# 06_-_HDMI_OUTPUT.net
KiCad netlist of a schematic drawn in Altium Designer
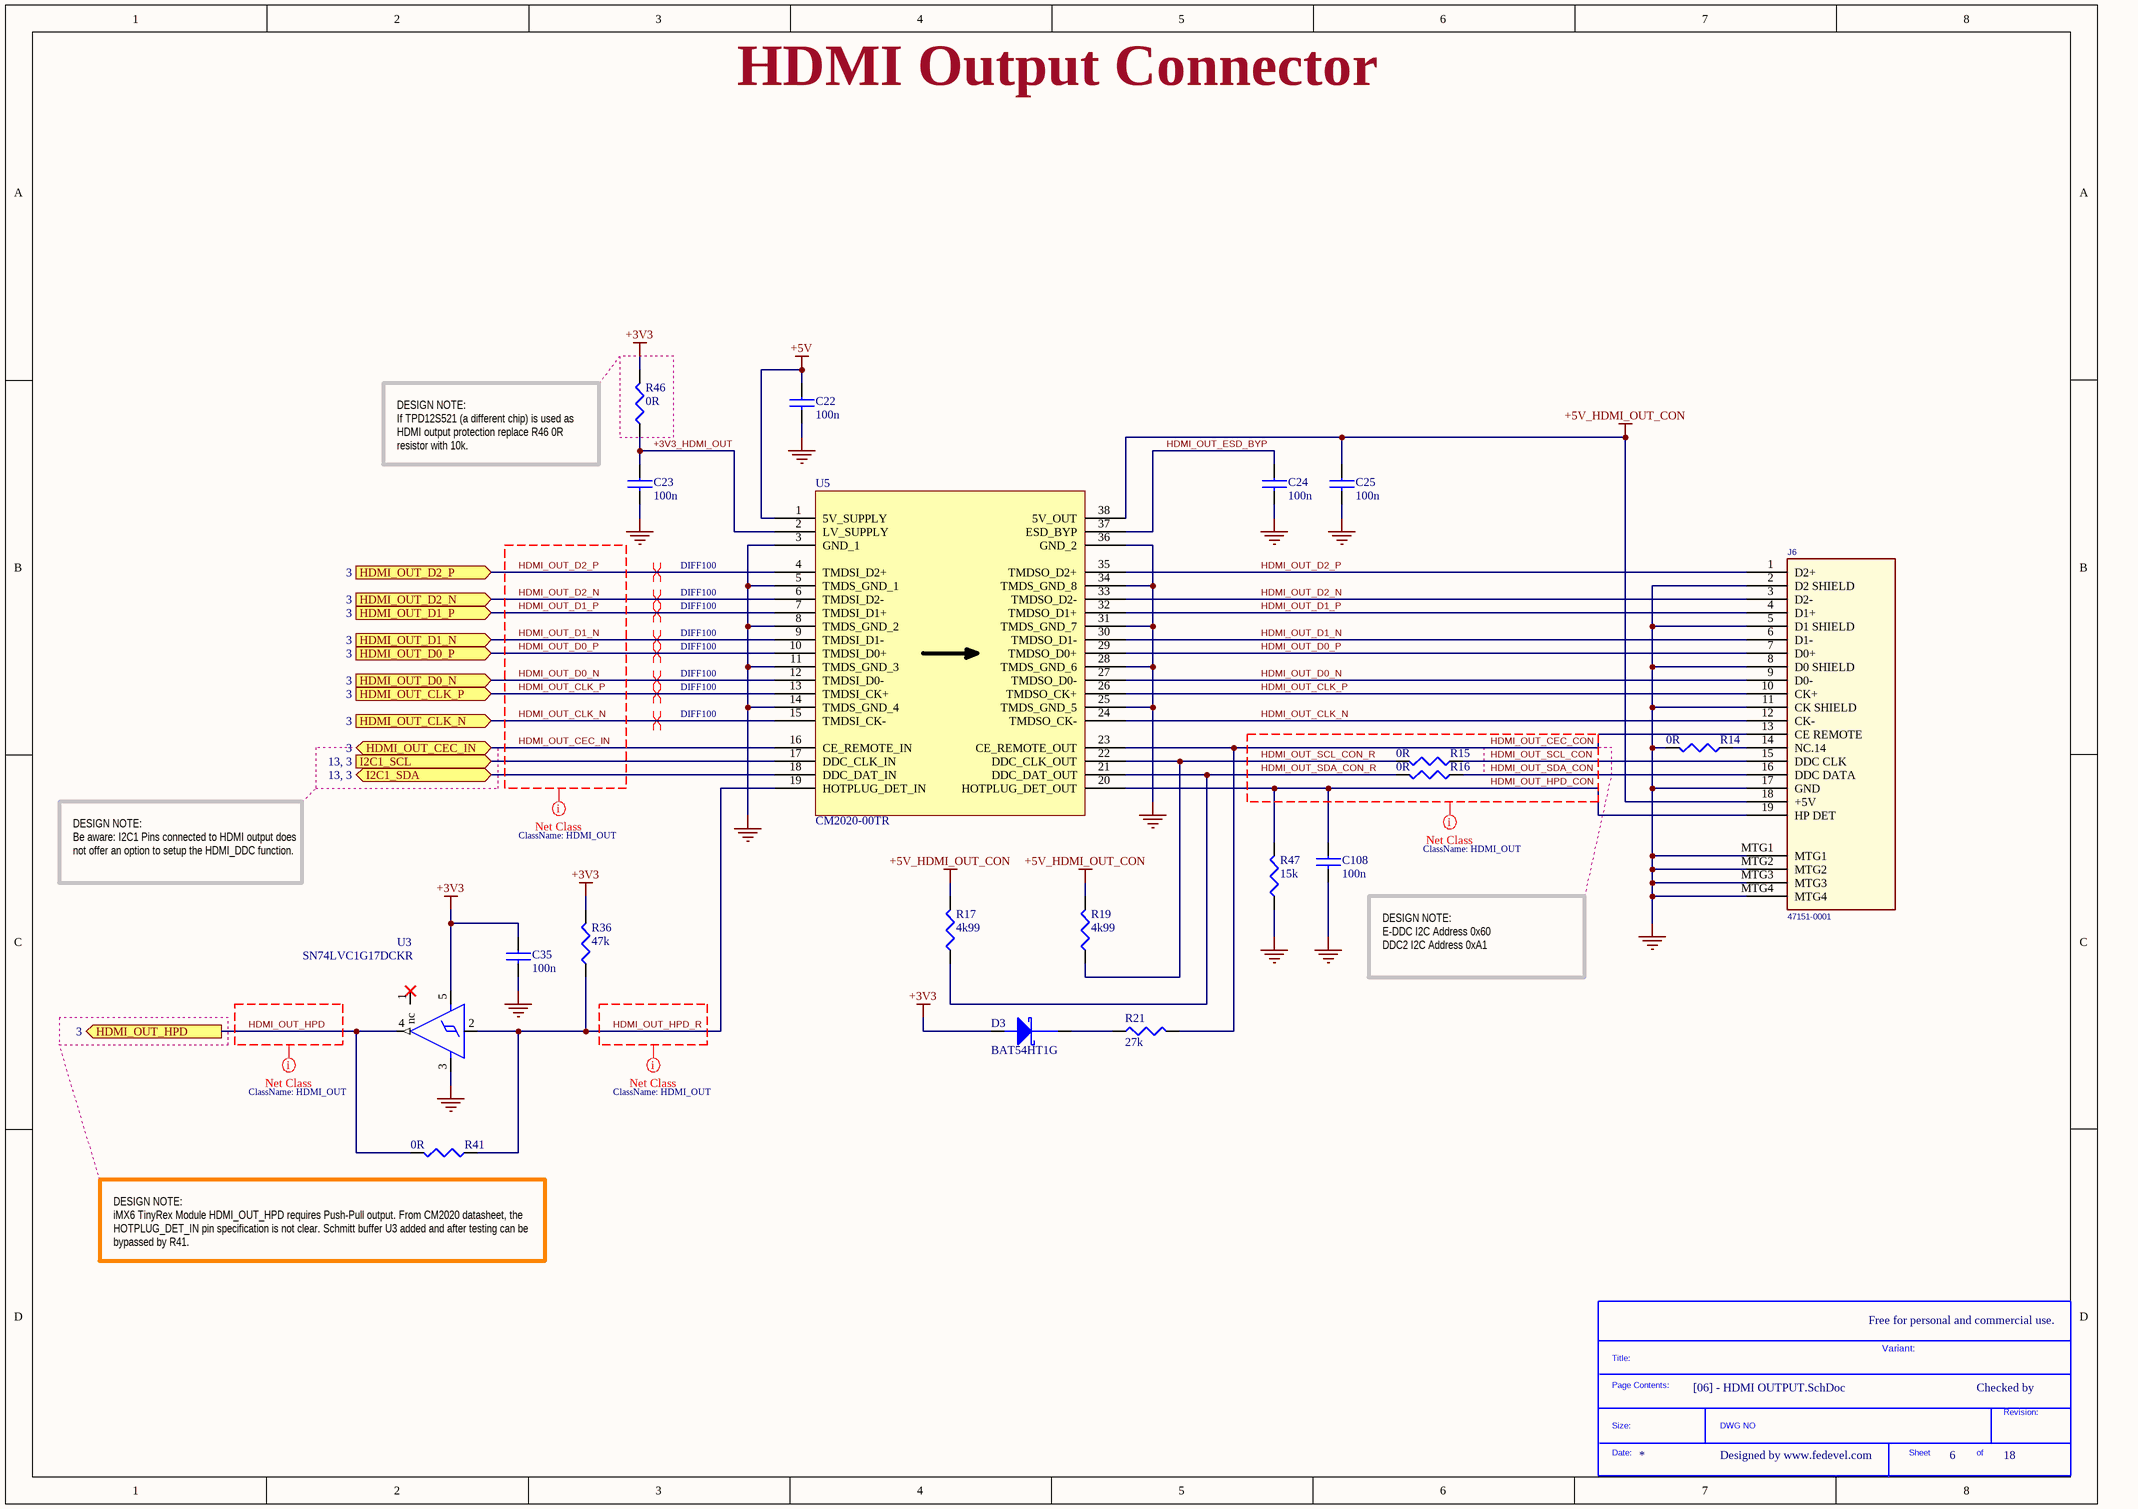
[diagram p0: [06] - HDMI OUTPUT.SchDoc]

(export (version "E")
  (design (tool "Eeschema 10.0.6"))
  (components
    (comp (ref "*") (value "SDTitleBlock") (libsource (lib "*") (part "SDTitleBlock")))
    (comp (ref "C22")
      (value "100n")
      (footprint "C0402")
      (description "CAP CER .10UF 50V X5R 10% 0402")
      (fields
        (field (name "MANUFACTURER") "TDK Corporation")
        (field (name "MANUFACTURER PART NUMBER") "C1005X5R1H104K")
      )
      (libsource (lib "Integrated_Library_FEDEVEL_APR_2015") (part "C1005X5R1H104K"))
    )
    (comp (ref "C23")
      (value "100n")
      (footprint "C0402")
      (description "CAP CER .10UF 50V X5R 10% 0402")
      (fields
        (field (name "MANUFACTURER") "TDK Corporation")
        (field (name "MANUFACTURER PART NUMBER") "C1005X5R1H104K")
      )
      (libsource (lib "Integrated_Library_FEDEVEL_APR_2015") (part "C1005X5R1H104K"))
    )
    (comp (ref "C24")
      (value "100n")
      (footprint "C0402")
      (description "CAP CER .10UF 50V X5R 10% 0402")
      (fields
        (field (name "MANUFACTURER") "TDK Corporation")
        (field (name "MANUFACTURER PART NUMBER") "C1005X5R1H104K")
      )
      (libsource (lib "Integrated_Library_FEDEVEL_APR_2015") (part "C1005X5R1H104K"))
    )
    (comp (ref "C25")
      (value "100n")
      (footprint "C0402")
      (description "CAP CER .10UF 50V X5R 10% 0402")
      (fields
        (field (name "MANUFACTURER") "TDK Corporation")
        (field (name "MANUFACTURER PART NUMBER") "C1005X5R1H104K")
      )
      (libsource (lib "Integrated_Library_FEDEVEL_APR_2015") (part "C1005X5R1H104K"))
    )
    (comp (ref "C35")
      (value "100n")
      (footprint "C0402")
      (description "CAP CER .10UF 50V X5R 10% 0402")
      (fields
        (field (name "MANUFACTURER") "TDK Corporation")
        (field (name "MANUFACTURER PART NUMBER") "C1005X5R1H104K")
      )
      (libsource (lib "Integrated_Library_FEDEVEL_APR_2015") (part "C1005X5R1H104K"))
    )
    (comp (ref "C108")
      (value "100n")
      (footprint "C0402")
      (description "CAP CER .10UF 50V X5R 10% 0402")
      (fields
        (field (name "MANUFACTURER") "TDK Corporation")
        (field (name "MANUFACTURER PART NUMBER") "C1005X5R1H104K")
      )
      (libsource (lib "Integrated_Library_FEDEVEL_APR_2015") (part "C1005X5R1H104K"))
    )
    (comp (ref "D3")
      (value "BAT54HT1G")
      (footprint "SOD323")
      (description "DIODE SCHOTTKY 30V 0.2A SOD323")
      (fields (field (name "MANUFACTURER") "Fairchild Semiconductor") (field (name ".CREATOR") "MM"))
      (libsource (lib "Integrated_Library_FEDEVEL_APR_2015") (part "BAT54HT1G"))
    )
    (comp (ref "J6")
      (value "47151-0001")
      (footprint "HDMI V1.1")
      (description "CONN RCPT 19POS HDMI RT ANG SMD")
      (fields
        (field (name "MANUFACTURER") "Molex Connector Corporation")
        (field (name ".CHECKED PCB") "MM")
        (field (name ".CHECKED SCH") "MM")
      )
      (libsource (lib "Integrated_Library_FEDEVEL_APR_2015") (part "47151-0001_v1.1"))
    )
    (comp (ref "R14")
      (value "0R")
      (footprint "R0402")
      (description "RES 0.0 OHM 1/16W 0402 SMD")
      (fields
        (field (name "MANUFACTURER") "Yageo")
        (field (name "MANUFACTURER PART NUMBER") "RC0402JR-070RL")
      )
      (libsource (lib "Integrated_Library_FEDEVEL_APR_2015") (part "RC0402JR-070RL"))
    )
    (comp (ref "R15")
      (value "0R")
      (footprint "R0402")
      (description "RES 0.0 OHM 1/16W 0402 SMD")
      (fields
        (field (name "MANUFACTURER") "Yageo")
        (field (name "MANUFACTURER PART NUMBER") "RC0402JR-070RL")
      )
      (libsource (lib "Integrated_Library_FEDEVEL_APR_2015") (part "RC0402JR-070RL"))
    )
    (comp (ref "R16")
      (value "0R")
      (footprint "R0402")
      (description "RES 0.0 OHM 1/16W 0402 SMD")
      (fields
        (field (name "MANUFACTURER") "Yageo")
        (field (name "MANUFACTURER PART NUMBER") "RC0402JR-070RL")
      )
      (libsource (lib "Integrated_Library_FEDEVEL_APR_2015") (part "RC0402JR-070RL"))
    )
    (comp (ref "R17")
      (value "4k99")
      (footprint "R0402")
      (description "RES TF 4.99K OHM 1% 1/16W 0402")
      (fields
        (field (name "MANUFACTURER") "Stackpole Electronics Inc")
        (field (name "MANUFACTURER PART NUMBER") "RMCF0402FT4K99")
      )
      (libsource (lib "Integrated_Library_FEDEVEL_APR_2015") (part "RMCF0402FT4K99"))
    )
    (comp (ref "R19")
      (value "4k99")
      (footprint "R0402")
      (description "RES TF 4.99K OHM 1% 1/16W 0402")
      (fields
        (field (name "MANUFACTURER") "Stackpole Electronics Inc")
        (field (name "MANUFACTURER PART NUMBER") "RMCF0402FT4K99")
      )
      (libsource (lib "Integrated_Library_FEDEVEL_APR_2015") (part "RMCF0402FT4K99"))
    )
    (comp (ref "R21")
      (value "27k")
      (footprint "R0402")
      (description "RES 27.0K OHM 1/16W 1% 0402 SMD")
      (fields
        (field (name "MANUFACTURER") "Yageo")
        (field (name "MANUFACTURER PART NUMBER") "RC0402FR-0727KL")
      )
      (libsource (lib "Integrated_Library_FEDEVEL_APR_2015") (part "RC0402FR-0727KL"))
    )
    (comp (ref "R36")
      (value "47k")
      (footprint "R0402")
      (description "RES 47.0K OHM 1/16W 1% 0402 SMD")
      (fields
        (field (name "MANUFACTURER") "Yageo")
        (field (name "MANUFACTURER PART NUMBER") "RC0402FR-0747KL")
      )
      (libsource (lib "Integrated_Library_FEDEVEL_APR_2015") (part "RC0402FR-0747KL"))
    )
    (comp (ref "R41")
      (value "0R")
      (footprint "R0402")
      (description "RES 0.0 OHM 1/16W 0402 SMD")
      (fields
        (field (name "MANUFACTURER") "Yageo")
        (field (name "MANUFACTURER PART NUMBER") "RC0402JR-070RL")
      )
      (libsource (lib "Integrated_Library_FEDEVEL_APR_2015") (part "RC0402JR-070RL"))
    )
    (comp (ref "R46")
      (value "0R")
      (footprint "R0402")
      (description "RES 0.0 OHM 1/16W 0402 SMD")
      (fields
        (field (name "MANUFACTURER") "Yageo")
        (field (name "MANUFACTURER PART NUMBER") "RC0402JR-070RL")
      )
      (libsource (lib "Integrated_Library_FEDEVEL_APR_2015") (part "RC0402JR-070RL"))
    )
    (comp (ref "R47")
      (value "15k")
      (footprint "R0402")
      (description "RES 15.0K OHM 1/16W 1% 0402 SMD")
      (fields
        (field (name "MANUFACTURER") "Yageo")
        (field (name "MANUFACTURER PART NUMBER") "RC0402FR-0715KL")
      )
      (libsource (lib "Integrated_Library_FEDEVEL_APR_2015") (part "RC0402FR-0715KL"))
    )
    (comp (ref "U3")
      (value "SN74LVC1G17DCKR")
      (footprint "SC70_5")
      (description "IC BUFFER SCHMIT TRIG SC705")
      (fields
        (field (name "MANUFACTURER") "Texas Instruments")
        (field (name ".CHECKED PCB") "RF")
        (field (name ".CHECKED SCH") "RF")
      )
      (libsource (lib "Integrated_Library_FEDEVEL_APR_2015") (part "SN74LVC1G17DCKR"))
    )
    (comp (ref "U5")
      (value "CM2020-00TR")
      (footprint "TSSOP_38")
      (description "IC HDMI TX PORT P/I 38-TSSOP")
      (fields (field (name "MANUFACTURER") "ON Semiconductor") (field (name ".CREATOR") "MM"))
      (libsource (lib "Integrated_Library_FEDEVEL_APR_2015") (part "CM2020-00TR"))
    )
  )
  (nets
    (net (code "1") (name "+3V3") (class "Default")
      (node (ref "C35") (pin "1") (pinfunction "1_1") (pintype "passive"))
      (node (ref "D3") (pin "2") (pinfunction "Anode_2") (pintype "passive"))
      (node (ref "R36") (pin "2") (pinfunction "2_2") (pintype "passive"))
      (node (ref "R46") (pin "2") (pinfunction "2_2") (pintype "passive"))
      (node (ref "U3") (pin "5") (pinfunction "NC1_5") (pintype "passive"))
    )
    (net (code "2") (name "+5V") (class "Default")
      (node (ref "C22") (pin "1") (pinfunction "1_1") (pintype "passive"))
      (node (ref "U5") (pin "1") (pinfunction "5V_SUPPLY_1") (pintype "passive"))
    )
    (net (code "3") (name "+5V_HDMI_OUT_CON") (class "Default")
      (node (ref "C25") (pin "1") (pinfunction "1_1") (pintype "passive"))
      (node (ref "J6") (pin "18") (pinfunction "+5V_18") (pintype "passive"))
      (node (ref "R17") (pin "2") (pinfunction "2_2") (pintype "passive"))
      (node (ref "R19") (pin "2") (pinfunction "2_2") (pintype "passive"))
      (node (ref "U5") (pin "38") (pinfunction "5V_OUT_38") (pintype "passive"))
    )
    (net (code "4") (name "/+3V3_HDMI_OUT") (class "Default")
      (node (ref "C23") (pin "1") (pinfunction "1_1") (pintype "passive"))
      (node (ref "R46") (pin "1") (pinfunction "1_1") (pintype "passive"))
      (node (ref "U5") (pin "2") (pinfunction "LV_SUPPLY_2") (pintype "passive"))
    )
    (net (code "5") (name "/HDMI_OUT_CEC_CON") (class "Default")
      (node (ref "J6") (pin "13") (pinfunction "CE_REMOTE_13") (pintype "passive"))
      (node (ref "R21") (pin "2") (pinfunction "2_2") (pintype "passive"))
      (node (ref "U5") (pin "23") (pinfunction "CE_REMOTE_OUT_23") (pintype "passive"))
    )
    (net (code "6") (name "/HDMI_OUT_CEC_IN") (class "Default")
      (node (ref "U5") (pin "16") (pinfunction "CE_REMOTE_IN_16") (pintype "passive"))
    )
    (net (code "7") (name "/HDMI_OUT_CLK_N") (class "Default")
      (node (ref "J6") (pin "12") (pinfunction "CK-_12") (pintype "passive"))
      (node (ref "U5") (pin "15") (pinfunction "TMDSI_CK-_15") (pintype "passive"))
      (node (ref "U5") (pin "24") (pinfunction "TMDSO_CK-_24") (pintype "passive"))
    )
    (net (code "8") (name "/HDMI_OUT_CLK_P") (class "Default")
      (node (ref "J6") (pin "10") (pinfunction "CK+_10") (pintype "passive"))
      (node (ref "U5") (pin "13") (pinfunction "TMDSI_CK+_13") (pintype "passive"))
      (node (ref "U5") (pin "26") (pinfunction "TMDSO_CK+_26") (pintype "passive"))
    )
    (net (code "9") (name "/HDMI_OUT_D0_N") (class "Default")
      (node (ref "J6") (pin "9") (pinfunction "D0-_9") (pintype "passive"))
      (node (ref "U5") (pin "12") (pinfunction "TMDSI_D0-_12") (pintype "passive"))
      (node (ref "U5") (pin "27") (pinfunction "TMDSO_D0-_27") (pintype "passive"))
    )
    (net (code "10") (name "/HDMI_OUT_D0_P") (class "Default")
      (node (ref "J6") (pin "7") (pinfunction "D0+_7") (pintype "passive"))
      (node (ref "U5") (pin "10") (pinfunction "TMDSI_D0+_10") (pintype "passive"))
      (node (ref "U5") (pin "29") (pinfunction "TMDSO_D0+_29") (pintype "passive"))
    )
    (net (code "11") (name "/HDMI_OUT_D1_N") (class "Default")
      (node (ref "J6") (pin "6") (pinfunction "D1-_6") (pintype "passive"))
      (node (ref "U5") (pin "30") (pinfunction "TMDSO_D1-_30") (pintype "passive"))
      (node (ref "U5") (pin "9") (pinfunction "TMDSI_D1-_9") (pintype "passive"))
    )
    (net (code "12") (name "/HDMI_OUT_D1_P") (class "Default")
      (node (ref "J6") (pin "4") (pinfunction "D1+_4") (pintype "passive"))
      (node (ref "U5") (pin "32") (pinfunction "TMDSO_D1+_32") (pintype "passive"))
      (node (ref "U5") (pin "7") (pinfunction "TMDSI_D1+_7") (pintype "passive"))
    )
    (net (code "13") (name "/HDMI_OUT_D2_N") (class "Default")
      (node (ref "J6") (pin "3") (pinfunction "D2-_3") (pintype "passive"))
      (node (ref "U5") (pin "33") (pinfunction "TMDSO_D2-_33") (pintype "passive"))
      (node (ref "U5") (pin "6") (pinfunction "TMDSI_D2-_6") (pintype "passive"))
    )
    (net (code "14") (name "/HDMI_OUT_D2_P") (class "Default")
      (node (ref "J6") (pin "1") (pinfunction "D2+_1") (pintype "passive"))
      (node (ref "U5") (pin "35") (pinfunction "TMDSO_D2+_35") (pintype "passive"))
      (node (ref "U5") (pin "4") (pinfunction "TMDSI_D2+_4") (pintype "passive"))
    )
    (net (code "15") (name "/HDMI_OUT_ESD_BYP") (class "Default")
      (node (ref "C24") (pin "1") (pinfunction "1_1") (pintype "passive"))
      (node (ref "U5") (pin "37") (pinfunction "ESD_BYP_37") (pintype "passive"))
    )
    (net (code "16") (name "/HDMI_OUT_HPD") (class "Default")
      (node (ref "R41") (pin "2") (pinfunction "2_2") (pintype "passive"))
      (node (ref "U3") (pin "4") (pinfunction "O_4") (pintype "output"))
    )
    (net (code "17") (name "/HDMI_OUT_HPD_CON") (class "Default")
      (node (ref "C108") (pin "1") (pinfunction "1_1") (pintype "passive"))
      (node (ref "J6") (pin "19") (pinfunction "HP_DET_19") (pintype "passive"))
      (node (ref "R47") (pin "2") (pinfunction "2_2") (pintype "passive"))
      (node (ref "U5") (pin "20") (pinfunction "HOTPLUG_DET_OUT_20") (pintype "passive"))
    )
    (net (code "18") (name "/HDMI_OUT_HPD_R") (class "Default")
      (node (ref "R36") (pin "1") (pinfunction "1_1") (pintype "passive"))
      (node (ref "R41") (pin "1") (pinfunction "1_1") (pintype "passive"))
      (node (ref "U3") (pin "2") (pinfunction "I_2") (pintype "passive"))
      (node (ref "U5") (pin "19") (pinfunction "HOTPLUG_DET_IN_19") (pintype "passive"))
    )
    (net (code "19") (name "/HDMI_OUT_SCL_CON") (class "Default")
      (node (ref "J6") (pin "15") (pinfunction "DDC_CLK_15") (pintype "passive"))
      (node (ref "R15") (pin "1") (pinfunction "1_1") (pintype "passive"))
    )
    (net (code "20") (name "/HDMI_OUT_SCL_CON_R") (class "Default")
      (node (ref "R15") (pin "2") (pinfunction "2_2") (pintype "passive"))
      (node (ref "R19") (pin "1") (pinfunction "1_1") (pintype "passive"))
      (node (ref "U5") (pin "22") (pinfunction "DDC_CLK_OUT_22") (pintype "passive"))
    )
    (net (code "21") (name "/HDMI_OUT_SDA_CON") (class "Default")
      (node (ref "J6") (pin "16") (pinfunction "DDC_DATA_16") (pintype "passive"))
      (node (ref "R16") (pin "1") (pinfunction "1_1") (pintype "passive"))
    )
    (net (code "22") (name "/HDMI_OUT_SDA_CON_R") (class "Default")
      (node (ref "R16") (pin "2") (pinfunction "2_2") (pintype "passive"))
      (node (ref "R17") (pin "1") (pinfunction "1_1") (pintype "passive"))
      (node (ref "U5") (pin "21") (pinfunction "DDC_DAT_OUT_21") (pintype "passive"))
    )
    (net (code "23") (name "/I2C1_SCL") (class "Default")
      (node (ref "U5") (pin "17") (pinfunction "DDC_CLK_IN_17") (pintype "passive"))
    )
    (net (code "24") (name "/I2C1_SDA") (class "Default")
      (node (ref "U5") (pin "18") (pinfunction "DDC_DAT_IN_18") (pintype "passive"))
    )
    (net (code "25") (name "GND") (class "Default")
      (node (ref "C108") (pin "2") (pinfunction "2_2") (pintype "passive"))
      (node (ref "C22") (pin "2") (pinfunction "2_2") (pintype "passive"))
      (node (ref "C23") (pin "2") (pinfunction "2_2") (pintype "passive"))
      (node (ref "C24") (pin "2") (pinfunction "2_2") (pintype "passive"))
      (node (ref "C25") (pin "2") (pinfunction "2_2") (pintype "passive"))
      (node (ref "C35") (pin "2") (pinfunction "2_2") (pintype "passive"))
      (node (ref "J6") (pin "11") (pinfunction "CK_SHIELD_11") (pintype "passive"))
      (node (ref "J6") (pin "17") (pinfunction "GND_17") (pintype "passive"))
      (node (ref "J6") (pin "2") (pinfunction "D2_SHIELD_2") (pintype "passive"))
      (node (ref "J6") (pin "5") (pinfunction "D1_SHIELD_5") (pintype "passive"))
      (node (ref "J6") (pin "8") (pinfunction "D0_SHIELD_8") (pintype "passive"))
      (node (ref "J6") (pin "MTG1") (pinfunction "MTG1_MTG1") (pintype "passive"))
      (node (ref "J6") (pin "MTG2") (pinfunction "MTG2_MTG2") (pintype "passive"))
      (node (ref "J6") (pin "MTG3") (pinfunction "MTG3_MTG3") (pintype "passive"))
      (node (ref "J6") (pin "MTG4") (pinfunction "MTG4_MTG4") (pintype "passive"))
      (node (ref "R14") (pin "2") (pinfunction "2_2") (pintype "passive"))
      (node (ref "R47") (pin "1") (pinfunction "1_1") (pintype "passive"))
      (node (ref "U3") (pin "3") (pinfunction "GND_3") (pintype "passive"))
      (node (ref "U5") (pin "11") (pinfunction "TMDS_GND_3_11") (pintype "passive"))
      (node (ref "U5") (pin "14") (pinfunction "TMDS_GND_4_14") (pintype "passive"))
      (node (ref "U5") (pin "25") (pinfunction "TMDS_GND_5_25") (pintype "passive"))
      (node (ref "U5") (pin "28") (pinfunction "TMDS_GND_6_28") (pintype "passive"))
      (node (ref "U5") (pin "3") (pinfunction "GND_1_3") (pintype "passive"))
      (node (ref "U5") (pin "31") (pinfunction "TMDS_GND_7_31") (pintype "passive"))
      (node (ref "U5") (pin "34") (pinfunction "TMDS_GND_8_34") (pintype "passive"))
      (node (ref "U5") (pin "36") (pinfunction "GND_2_36") (pintype "passive"))
      (node (ref "U5") (pin "5") (pinfunction "TMDS_GND_1_5") (pintype "passive"))
      (node (ref "U5") (pin "8") (pinfunction "TMDS_GND_2_8") (pintype "passive"))
    )
    (net (code "26") (name "Net-(D3-Cathode)") (class "Default")
      (node (ref "D3") (pin "1") (pinfunction "Cathode_1") (pintype "passive"))
      (node (ref "R21") (pin "1") (pinfunction "1_1") (pintype "passive"))
    )
    (net (code "27") (name "Net-(J6-NC.14)") (class "Default")
      (node (ref "J6") (pin "14") (pinfunction "NC.14_14") (pintype "passive"))
      (node (ref "R14") (pin "1") (pinfunction "1_1") (pintype "passive"))
    )
    (net (code "28") (name "unconnected-(U3-nc-Pad1)") (class "Default")
      (node (ref "U3") (pin "1") (pinfunction "nc_1") (pintype "passive+no_connect"))
    )
  )
)
